# baru.net
KiCad netlist of a schematic drawn in EAGLE
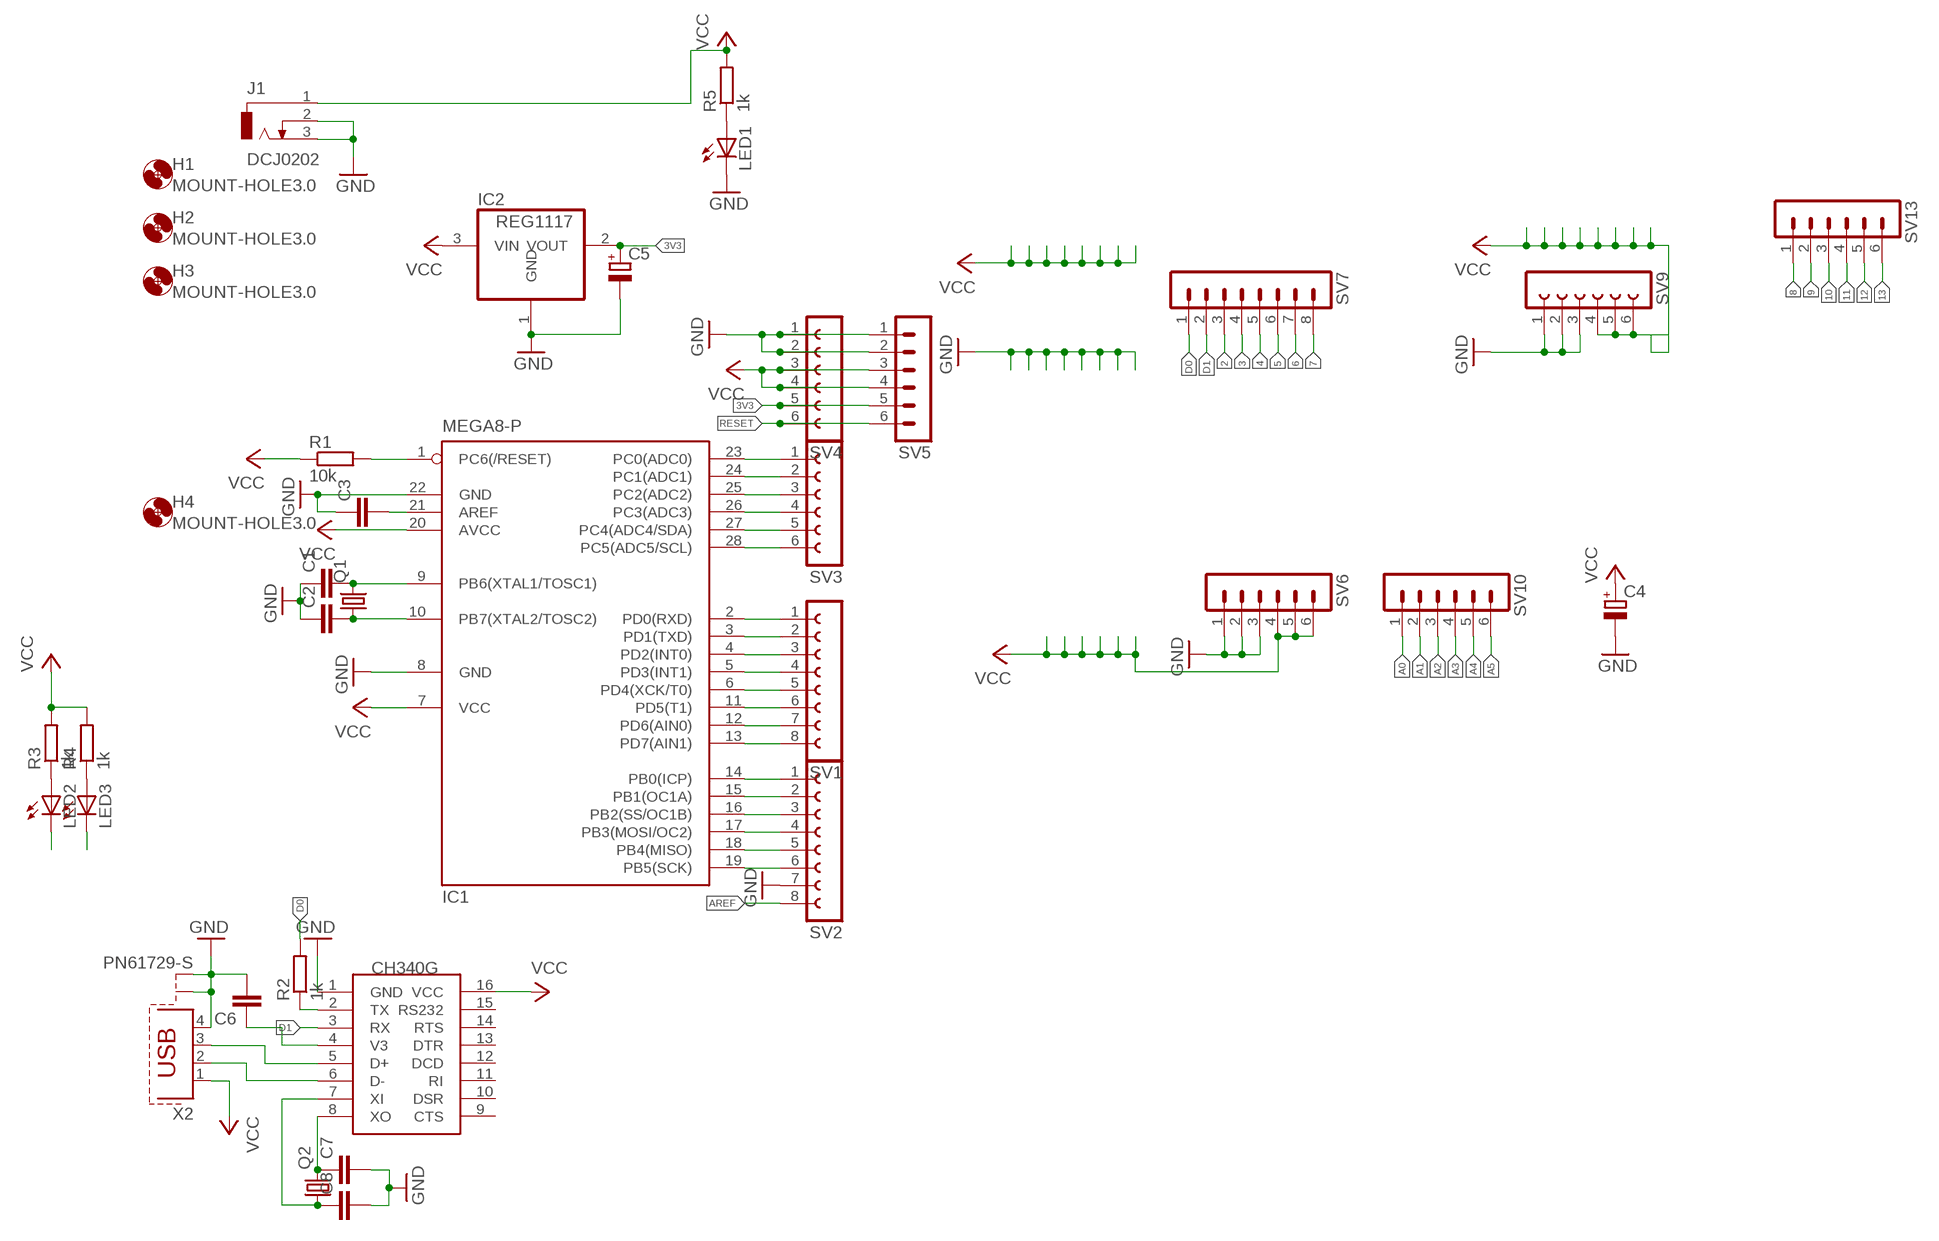
[diagram p0: schematic, sheet 1]

(export (version "E")
  (design (tool "Eeschema 10.0.6"))
  (components
    (comp (ref "C1")
      (value "C-EU025-025X050")
      (footprint "eagle-import:C025-025X050")
      (libsource (lib "eagle-import") (part "C-EU025-025X050"))
    )
    (comp (ref "C2")
      (value "C-EU025-025X050")
      (footprint "eagle-import:C025-025X050")
      (libsource (lib "eagle-import") (part "C-EU025-025X050"))
    )
    (comp (ref "C3")
      (value "C-EU050-024X044")
      (footprint "eagle-import:C050-024X044")
      (libsource (lib "eagle-import") (part "C-EU050-024X044"))
    )
    (comp (ref "C4")
      (value "CPOL-EUE2.5-7")
      (footprint "eagle-import:E2,5-7")
      (libsource (lib "eagle-import") (part "CPOL-EUE2.5-7"))
    )
    (comp (ref "C5")
      (value "CPOL-EUE2.5-5")
      (footprint "eagle-import:E2,5-5")
      (libsource (lib "eagle-import") (part "CPOL-EUE2.5-5"))
    )
    (comp (ref "C6")
      (value "C-EU050-024X044")
      (footprint "eagle-import:C050-024X044")
      (libsource (lib "eagle-import") (part "C-EU050-024X044"))
    )
    (comp (ref "C7")
      (value "C-EU025-025X050")
      (footprint "eagle-import:C025-025X050")
      (libsource (lib "eagle-import") (part "C-EU025-025X050"))
    )
    (comp (ref "C8")
      (value "C-EU025-025X050")
      (footprint "eagle-import:C025-025X050")
      (libsource (lib "eagle-import") (part "C-EU025-025X050"))
    )
    (comp (ref "H1")
      (value "MOUNT-HOLE3.0")
      (footprint "eagle-import:3,0")
      (libsource (lib "eagle-import") (part "MOUNT-HOLE3.0"))
    )
    (comp (ref "H2")
      (value "MOUNT-HOLE3.0")
      (footprint "eagle-import:3,0")
      (libsource (lib "eagle-import") (part "MOUNT-HOLE3.0"))
    )
    (comp (ref "H3")
      (value "MOUNT-HOLE3.0")
      (footprint "eagle-import:3,0")
      (libsource (lib "eagle-import") (part "MOUNT-HOLE3.0"))
    )
    (comp (ref "H4")
      (value "MOUNT-HOLE3.0")
      (footprint "eagle-import:3,0")
      (libsource (lib "eagle-import") (part "MOUNT-HOLE3.0"))
    )
    (comp (ref "IC1")
      (value "MEGA8-P")
      (footprint "eagle-import:DIL28-3")
      (libsource (lib "eagle-import") (part "MEGA8-P"))
    )
    (comp (ref "IC2")
      (value "REG1117")
      (footprint "eagle-import:SOT223")
      (libsource (lib "eagle-import") (part "REG1117"))
    )
    (comp (ref "J1")
      (value "DCJ0202")
      (footprint "eagle-import:DCJ0202")
      (libsource (lib "eagle-import") (part "DCJ0202"))
    )
    (comp (ref "LED1")
      (value "LED3MM")
      (footprint "eagle-import:LED3MM")
      (libsource (lib "eagle-import") (part "LED3MM"))
    )
    (comp (ref "LED2")
      (value "LED3MM")
      (footprint "eagle-import:LED3MM")
      (libsource (lib "eagle-import") (part "LED3MM"))
    )
    (comp (ref "LED3")
      (value "LED3MM")
      (footprint "eagle-import:LED3MM")
      (libsource (lib "eagle-import") (part "LED3MM"))
    )
    (comp (ref "Q1")
      (value "CRYSTALHC49S")
      (footprint "eagle-import:HC49_S")
      (libsource (lib "eagle-import") (part "CRYSTALHC49S"))
    )
    (comp (ref "Q2")
      (value "CRYSTALHC49S")
      (footprint "eagle-import:HC49_S")
      (libsource (lib "eagle-import") (part "CRYSTALHC49S"))
    )
    (comp (ref "R1")
      (value "10k")
      (footprint "eagle-import:0207_10")
      (libsource (lib "eagle-import") (part "R-EU_0207/10"))
    )
    (comp (ref "R2")
      (value "1k")
      (footprint "eagle-import:0207_10")
      (libsource (lib "eagle-import") (part "R-EU_0207/10"))
    )
    (comp (ref "R3")
      (value "1k")
      (footprint "eagle-import:0207_10")
      (libsource (lib "eagle-import") (part "R-EU_0207/10"))
    )
    (comp (ref "R4")
      (value "1k")
      (footprint "eagle-import:0207_10")
      (libsource (lib "eagle-import") (part "R-EU_0207/10"))
    )
    (comp (ref "R5")
      (value "1k")
      (footprint "eagle-import:0207_10")
      (libsource (lib "eagle-import") (part "R-EU_0207/10"))
    )
    (comp (ref "SV1")
      (value "FE08-1")
      (footprint "eagle-import:FE08")
      (libsource (lib "eagle-import") (part "FE08-1"))
    )
    (comp (ref "SV2")
      (value "FE08-1")
      (footprint "eagle-import:FE08")
      (libsource (lib "eagle-import") (part "FE08-1"))
    )
    (comp (ref "SV3")
      (value "FE06-1")
      (footprint "eagle-import:FE06")
      (libsource (lib "eagle-import") (part "FE06-1"))
    )
    (comp (ref "SV4")
      (value "FE06-1")
      (footprint "eagle-import:FE06")
      (libsource (lib "eagle-import") (part "FE06-1"))
    )
    (comp (ref "SV5")
      (value "MA06-1")
      (footprint "eagle-import:MA06-1")
      (libsource (lib "eagle-import") (part "MA06-1"))
    )
    (comp (ref "SV6")
      (value "MA06-1")
      (footprint "eagle-import:MA06-1")
      (libsource (lib "eagle-import") (part "MA06-1"))
    )
    (comp (ref "SV7")
      (value "MA08-1")
      (footprint "eagle-import:MA08-1")
      (libsource (lib "eagle-import") (part "MA08-1"))
    )
    (comp (ref "SV9")
      (value "FE06-1")
      (footprint "eagle-import:FE06")
      (libsource (lib "eagle-import") (part "FE06-1"))
    )
    (comp (ref "SV10")
      (value "MA06-1")
      (footprint "eagle-import:MA06-1")
      (libsource (lib "eagle-import") (part "MA06-1"))
    )
    (comp (ref "SV13")
      (value "MA06-1")
      (footprint "eagle-import:MA06-1")
      (libsource (lib "eagle-import") (part "MA06-1"))
    )
    (comp (ref "U$1")
      (value "CH340G")
      (footprint "eagle-import:SOIC16")
      (libsource (lib "eagle-import") (part "CH340G"))
    )
    (comp (ref "X2")
      (value "PN61729-S")
      (footprint "eagle-import:PN61729-S")
      (libsource (lib "eagle-import") (part "PN61729-S"))
    )
  )
  (nets
    (net (code "1") (name "/TX") (class "Default")
      (node (ref "LED3") (pin "K") (pinfunction "C_K") (pintype "passive"))
      (node (ref "R2") (pin "1") (pinfunction "1_1") (pintype "passive"))
      (node (ref "U$1") (pin "2") (pinfunction "TX_2") (pintype "bidirectional"))
    )
    (net (code "2") (name "2") (class "Default")
      (node (ref "IC1") (pin "4") (pinfunction "PD2(INT0)_4") (pintype "bidirectional"))
      (node (ref "SV1") (pin "3") (pinfunction "3_3") (pintype "passive"))
      (node (ref "SV7") (pin "3") (pinfunction "3_3") (pintype "passive"))
    )
    (net (code "3") (name "3") (class "Default")
      (node (ref "IC1") (pin "5") (pinfunction "PD3(INT1)_5") (pintype "bidirectional"))
      (node (ref "SV1") (pin "4") (pinfunction "4_4") (pintype "passive"))
      (node (ref "SV7") (pin "4") (pinfunction "4_4") (pintype "passive"))
    )
    (net (code "4") (name "3V3") (class "Default")
      (node (ref "C5") (pin "+") (pinfunction "+_+") (pintype "passive"))
      (node (ref "IC2") (pin "2") (pinfunction "VOUT_2") (pintype "output"))
      (node (ref "SV4") (pin "5") (pinfunction "5_5") (pintype "passive"))
      (node (ref "SV5") (pin "5") (pinfunction "5_5") (pintype "passive"))
    )
    (net (code "5") (name "4") (class "Default")
      (node (ref "IC1") (pin "6") (pinfunction "PD4(XCK/T0)_6") (pintype "bidirectional"))
      (node (ref "SV1") (pin "5") (pinfunction "5_5") (pintype "passive"))
      (node (ref "SV7") (pin "5") (pinfunction "5_5") (pintype "passive"))
    )
    (net (code "6") (name "5") (class "Default")
      (node (ref "IC1") (pin "11") (pinfunction "PD5(T1)_11") (pintype "bidirectional"))
      (node (ref "SV1") (pin "6") (pinfunction "6_6") (pintype "passive"))
      (node (ref "SV7") (pin "6") (pinfunction "6_6") (pintype "passive"))
    )
    (net (code "7") (name "6") (class "Default")
      (node (ref "IC1") (pin "12") (pinfunction "PD6(AIN0)_12") (pintype "bidirectional"))
      (node (ref "SV1") (pin "7") (pinfunction "7_7") (pintype "passive"))
      (node (ref "SV7") (pin "7") (pinfunction "7_7") (pintype "passive"))
    )
    (net (code "8") (name "7") (class "Default")
      (node (ref "IC1") (pin "13") (pinfunction "PD7(AIN1)_13") (pintype "bidirectional"))
      (node (ref "SV1") (pin "8") (pinfunction "8_8") (pintype "passive"))
      (node (ref "SV7") (pin "8") (pinfunction "8_8") (pintype "passive"))
    )
    (net (code "9") (name "8") (class "Default")
      (node (ref "IC1") (pin "14") (pinfunction "PB0(ICP)_14") (pintype "bidirectional"))
      (node (ref "SV13") (pin "1") (pinfunction "1_1") (pintype "passive"))
      (node (ref "SV2") (pin "1") (pinfunction "1_1") (pintype "passive"))
    )
    (net (code "10") (name "9") (class "Default")
      (node (ref "IC1") (pin "15") (pinfunction "PB1(OC1A)_15") (pintype "bidirectional"))
      (node (ref "SV13") (pin "2") (pinfunction "2_2") (pintype "passive"))
      (node (ref "SV2") (pin "2") (pinfunction "2_2") (pintype "passive"))
    )
    (net (code "11") (name "10") (class "Default")
      (node (ref "IC1") (pin "16") (pinfunction "PB2(SS/OC1B)_16") (pintype "bidirectional"))
      (node (ref "SV13") (pin "3") (pinfunction "3_3") (pintype "passive"))
      (node (ref "SV2") (pin "3") (pinfunction "3_3") (pintype "passive"))
    )
    (net (code "12") (name "11") (class "Default")
      (node (ref "IC1") (pin "17") (pinfunction "PB3(MOSI/OC2)_17") (pintype "bidirectional"))
      (node (ref "SV13") (pin "4") (pinfunction "4_4") (pintype "passive"))
      (node (ref "SV2") (pin "4") (pinfunction "4_4") (pintype "passive"))
    )
    (net (code "13") (name "12") (class "Default")
      (node (ref "IC1") (pin "18") (pinfunction "PB4(MISO)_18") (pintype "bidirectional"))
      (node (ref "SV13") (pin "5") (pinfunction "5_5") (pintype "passive"))
      (node (ref "SV2") (pin "5") (pinfunction "5_5") (pintype "passive"))
    )
    (net (code "14") (name "13") (class "Default")
      (node (ref "IC1") (pin "19") (pinfunction "PB5(SCK)_19") (pintype "bidirectional"))
      (node (ref "SV13") (pin "6") (pinfunction "6_6") (pintype "passive"))
      (node (ref "SV2") (pin "6") (pinfunction "6_6") (pintype "passive"))
    )
    (net (code "15") (name "A0") (class "Default")
      (node (ref "IC1") (pin "23") (pinfunction "PC0(ADC0)_23") (pintype "bidirectional"))
      (node (ref "SV10") (pin "1") (pinfunction "1_1") (pintype "passive"))
      (node (ref "SV3") (pin "1") (pinfunction "1_1") (pintype "passive"))
    )
    (net (code "16") (name "A1") (class "Default")
      (node (ref "IC1") (pin "24") (pinfunction "PC1(ADC1)_24") (pintype "bidirectional"))
      (node (ref "SV10") (pin "2") (pinfunction "2_2") (pintype "passive"))
      (node (ref "SV3") (pin "2") (pinfunction "2_2") (pintype "passive"))
    )
    (net (code "17") (name "A2") (class "Default")
      (node (ref "IC1") (pin "25") (pinfunction "PC2(ADC2)_25") (pintype "bidirectional"))
      (node (ref "SV10") (pin "3") (pinfunction "3_3") (pintype "passive"))
      (node (ref "SV3") (pin "3") (pinfunction "3_3") (pintype "passive"))
    )
    (net (code "18") (name "A3") (class "Default")
      (node (ref "IC1") (pin "26") (pinfunction "PC3(ADC3)_26") (pintype "bidirectional"))
      (node (ref "SV10") (pin "4") (pinfunction "4_4") (pintype "passive"))
      (node (ref "SV3") (pin "4") (pinfunction "4_4") (pintype "passive"))
    )
    (net (code "19") (name "A4") (class "Default")
      (node (ref "IC1") (pin "27") (pinfunction "PC4(ADC4/SDA)_27") (pintype "bidirectional"))
      (node (ref "SV10") (pin "5") (pinfunction "5_5") (pintype "passive"))
      (node (ref "SV3") (pin "5") (pinfunction "5_5") (pintype "passive"))
    )
    (net (code "20") (name "A5") (class "Default")
      (node (ref "IC1") (pin "28") (pinfunction "PC5(ADC5/SCL)_28") (pintype "bidirectional"))
      (node (ref "SV10") (pin "6") (pinfunction "6_6") (pintype "passive"))
      (node (ref "SV3") (pin "6") (pinfunction "6_6") (pintype "passive"))
    )
    (net (code "21") (name "AREF") (class "Default")
      (node (ref "C3") (pin "2") (pinfunction "2_2") (pintype "passive"))
      (node (ref "IC1") (pin "21") (pinfunction "AREF_21") (pintype "passive"))
      (node (ref "SV2") (pin "8") (pinfunction "8_8") (pintype "passive"))
    )
    (net (code "22") (name "D0") (class "Default")
      (node (ref "IC1") (pin "2") (pinfunction "PD0(RXD)_2") (pintype "bidirectional"))
      (node (ref "R2") (pin "2") (pinfunction "2_2") (pintype "passive"))
      (node (ref "SV1") (pin "1") (pinfunction "1_1") (pintype "passive"))
      (node (ref "SV7") (pin "1") (pinfunction "1_1") (pintype "passive"))
    )
    (net (code "23") (name "D1") (class "Default")
      (node (ref "IC1") (pin "3") (pinfunction "PD1(TXD)_3") (pintype "bidirectional"))
      (node (ref "LED2") (pin "K") (pinfunction "C_K") (pintype "passive"))
      (node (ref "SV1") (pin "2") (pinfunction "2_2") (pintype "passive"))
      (node (ref "SV7") (pin "2") (pinfunction "2_2") (pintype "passive"))
      (node (ref "U$1") (pin "3") (pinfunction "RX_3") (pintype "bidirectional"))
    )
    (net (code "24") (name "GND") (class "Default")
      (node (ref "C1") (pin "1") (pinfunction "1_1") (pintype "passive"))
      (node (ref "C2") (pin "1") (pinfunction "1_1") (pintype "passive"))
      (node (ref "C3") (pin "1") (pinfunction "1_1") (pintype "passive"))
      (node (ref "C4") (pin "-") (pinfunction "-_-") (pintype "passive"))
      (node (ref "C5") (pin "-") (pinfunction "-_-") (pintype "passive"))
      (node (ref "C6") (pin "2") (pinfunction "2_2") (pintype "passive"))
      (node (ref "C7") (pin "2") (pinfunction "2_2") (pintype "passive"))
      (node (ref "C8") (pin "2") (pinfunction "2_2") (pintype "passive"))
      (node (ref "IC1") (pin "22") (pinfunction "GND_22") (pintype "power_in"))
      (node (ref "IC1") (pin "8") (pinfunction "GND_8") (pintype "power_in"))
      (node (ref "IC2") (pin "1") (pinfunction "GND_1") (pintype "power_in"))
      (node (ref "J1") (pin "2") (pinfunction "2_2") (pintype "passive"))
      (node (ref "J1") (pin "3") (pinfunction "3_3") (pintype "passive"))
      (node (ref "LED1") (pin "K") (pinfunction "C_K") (pintype "passive"))
      (node (ref "SV2") (pin "7") (pinfunction "7_7") (pintype "passive"))
      (node (ref "SV4") (pin "1") (pinfunction "1_1") (pintype "passive"))
      (node (ref "SV4") (pin "2") (pinfunction "2_2") (pintype "passive"))
      (node (ref "SV5") (pin "1") (pinfunction "1_1") (pintype "passive"))
      (node (ref "SV5") (pin "2") (pinfunction "2_2") (pintype "passive"))
      (node (ref "SV6") (pin "1") (pinfunction "1_1") (pintype "passive"))
      (node (ref "SV6") (pin "2") (pinfunction "2_2") (pintype "passive"))
      (node (ref "SV6") (pin "3") (pinfunction "3_3") (pintype "passive"))
      (node (ref "SV9") (pin "1") (pinfunction "1_1") (pintype "passive"))
      (node (ref "SV9") (pin "2") (pinfunction "2_2") (pintype "passive"))
      (node (ref "SV9") (pin "3") (pinfunction "3_3") (pintype "passive"))
      (node (ref "U$1") (pin "1") (pinfunction "GND_1") (pintype "bidirectional"))
      (node (ref "X2") (pin "4") (pinfunction "4_4") (pintype "passive"))
      (node (ref "X2") (pin "S1") (pinfunction "S1_S1") (pintype "passive"))
      (node (ref "X2") (pin "S2") (pinfunction "S2_S2") (pintype "passive"))
    )
    (net (code "25") (name "Net-(IC1-PB6(XTAL1{slash}TOSC1))") (class "Default")
      (node (ref "C1") (pin "2") (pinfunction "2_2") (pintype "passive"))
      (node (ref "IC1") (pin "9") (pinfunction "PB6(XTAL1/TOSC1)_9") (pintype "bidirectional"))
      (node (ref "Q1") (pin "2") (pinfunction "2_2") (pintype "passive"))
    )
    (net (code "26") (name "Net-(IC1-PB7(XTAL2{slash}TOSC2))") (class "Default")
      (node (ref "C2") (pin "2") (pinfunction "2_2") (pintype "passive"))
      (node (ref "IC1") (pin "10") (pinfunction "PB7(XTAL2/TOSC2)_10") (pintype "bidirectional"))
      (node (ref "Q1") (pin "1") (pinfunction "1_1") (pintype "passive"))
    )
    (net (code "27") (name "Net-(LED1-PadA)") (class "Default")
      (node (ref "LED1") (pin "A") (pinfunction "A_A") (pintype "passive"))
      (node (ref "R5") (pin "1") (pinfunction "1_1") (pintype "passive"))
    )
    (net (code "28") (name "Net-(LED2-PadA)") (class "Default")
      (node (ref "LED2") (pin "A") (pinfunction "A_A") (pintype "passive"))
      (node (ref "R3") (pin "1") (pinfunction "1_1") (pintype "passive"))
    )
    (net (code "29") (name "Net-(LED3-PadA)") (class "Default")
      (node (ref "LED3") (pin "A") (pinfunction "A_A") (pintype "passive"))
      (node (ref "R4") (pin "1") (pinfunction "1_1") (pintype "passive"))
    )
    (net (code "30") (name "Net-(U$1-D+)") (class "Default")
      (node (ref "U$1") (pin "5") (pinfunction "D+_5") (pintype "bidirectional"))
      (node (ref "X2") (pin "3") (pinfunction "3_3") (pintype "passive"))
    )
    (net (code "31") (name "Net-(U$1-D-)") (class "Default")
      (node (ref "U$1") (pin "6") (pinfunction "D-_6") (pintype "bidirectional"))
      (node (ref "X2") (pin "2") (pinfunction "2_2") (pintype "passive"))
    )
    (net (code "32") (name "Net-(U$1-V3)") (class "Default")
      (node (ref "C6") (pin "1") (pinfunction "1_1") (pintype "passive"))
      (node (ref "U$1") (pin "4") (pinfunction "V3_4") (pintype "bidirectional"))
    )
    (net (code "33") (name "Net-(U$1-XI)") (class "Default")
      (node (ref "C8") (pin "1") (pinfunction "1_1") (pintype "passive"))
      (node (ref "Q2") (pin "1") (pinfunction "1_1") (pintype "passive"))
      (node (ref "U$1") (pin "7") (pinfunction "XI_7") (pintype "bidirectional"))
    )
    (net (code "34") (name "Net-(U$1-XO)") (class "Default")
      (node (ref "C7") (pin "1") (pinfunction "1_1") (pintype "passive"))
      (node (ref "Q2") (pin "2") (pinfunction "2_2") (pintype "passive"))
      (node (ref "U$1") (pin "8") (pinfunction "XO_8") (pintype "bidirectional"))
    )
    (net (code "35") (name "RESET") (class "Default")
      (node (ref "IC1") (pin "1") (pinfunction "PC6(/RESET)_1") (pintype "bidirectional"))
      (node (ref "R1") (pin "2") (pinfunction "2_2") (pintype "passive"))
      (node (ref "SV4") (pin "6") (pinfunction "6_6") (pintype "passive"))
      (node (ref "SV5") (pin "6") (pinfunction "6_6") (pintype "passive"))
    )
    (net (code "36") (name "VCC") (class "Default")
      (node (ref "C4") (pin "+") (pinfunction "+_+") (pintype "passive"))
      (node (ref "IC1") (pin "20") (pinfunction "AVCC_20") (pintype "power_in"))
      (node (ref "IC1") (pin "7") (pinfunction "VCC_7") (pintype "power_in"))
      (node (ref "IC2") (pin "3") (pinfunction "VIN_3") (pintype "input"))
      (node (ref "J1") (pin "1") (pinfunction "1_1") (pintype "passive"))
      (node (ref "R1") (pin "1") (pinfunction "1_1") (pintype "passive"))
      (node (ref "R3") (pin "2") (pinfunction "2_2") (pintype "passive"))
      (node (ref "R4") (pin "2") (pinfunction "2_2") (pintype "passive"))
      (node (ref "R5") (pin "2") (pinfunction "2_2") (pintype "passive"))
      (node (ref "SV4") (pin "3") (pinfunction "3_3") (pintype "passive"))
      (node (ref "SV4") (pin "4") (pinfunction "4_4") (pintype "passive"))
      (node (ref "SV5") (pin "3") (pinfunction "3_3") (pintype "passive"))
      (node (ref "SV5") (pin "4") (pinfunction "4_4") (pintype "passive"))
      (node (ref "SV6") (pin "4") (pinfunction "4_4") (pintype "passive"))
      (node (ref "SV6") (pin "5") (pinfunction "5_5") (pintype "passive"))
      (node (ref "SV6") (pin "6") (pinfunction "6_6") (pintype "passive"))
      (node (ref "SV9") (pin "4") (pinfunction "4_4") (pintype "passive"))
      (node (ref "SV9") (pin "5") (pinfunction "5_5") (pintype "passive"))
      (node (ref "SV9") (pin "6") (pinfunction "6_6") (pintype "passive"))
      (node (ref "U$1") (pin "16") (pinfunction "VCC_16") (pintype "bidirectional"))
      (node (ref "X2") (pin "1") (pinfunction "1_1") (pintype "passive"))
    )
    (net (code "37") (name "unconnected-(U$1-CTS-Pad9)") (class "Default")
      (node (ref "U$1") (pin "9") (pinfunction "CTS_9") (pintype "bidirectional"))
    )
    (net (code "38") (name "unconnected-(U$1-DCD-Pad12)") (class "Default")
      (node (ref "U$1") (pin "12") (pinfunction "DCD_12") (pintype "bidirectional"))
    )
    (net (code "39") (name "unconnected-(U$1-DSR-Pad10)") (class "Default")
      (node (ref "U$1") (pin "10") (pinfunction "DSR_10") (pintype "bidirectional"))
    )
    (net (code "40") (name "unconnected-(U$1-DTR-Pad13)") (class "Default")
      (node (ref "U$1") (pin "13") (pinfunction "DTR_13") (pintype "bidirectional"))
    )
    (net (code "41") (name "unconnected-(U$1-RI-Pad11)") (class "Default")
      (node (ref "U$1") (pin "11") (pinfunction "RI_11") (pintype "bidirectional"))
    )
    (net (code "42") (name "unconnected-(U$1-RS232-Pad15)") (class "Default")
      (node (ref "U$1") (pin "15") (pinfunction "RS232_15") (pintype "bidirectional"))
    )
    (net (code "43") (name "unconnected-(U$1-RTS-Pad14)") (class "Default")
      (node (ref "U$1") (pin "14") (pinfunction "RTS_14") (pintype "bidirectional"))
    )
  )
)
